# MCUio_v1_0.net
KiCad netlist of a schematic drawn in EAGLE
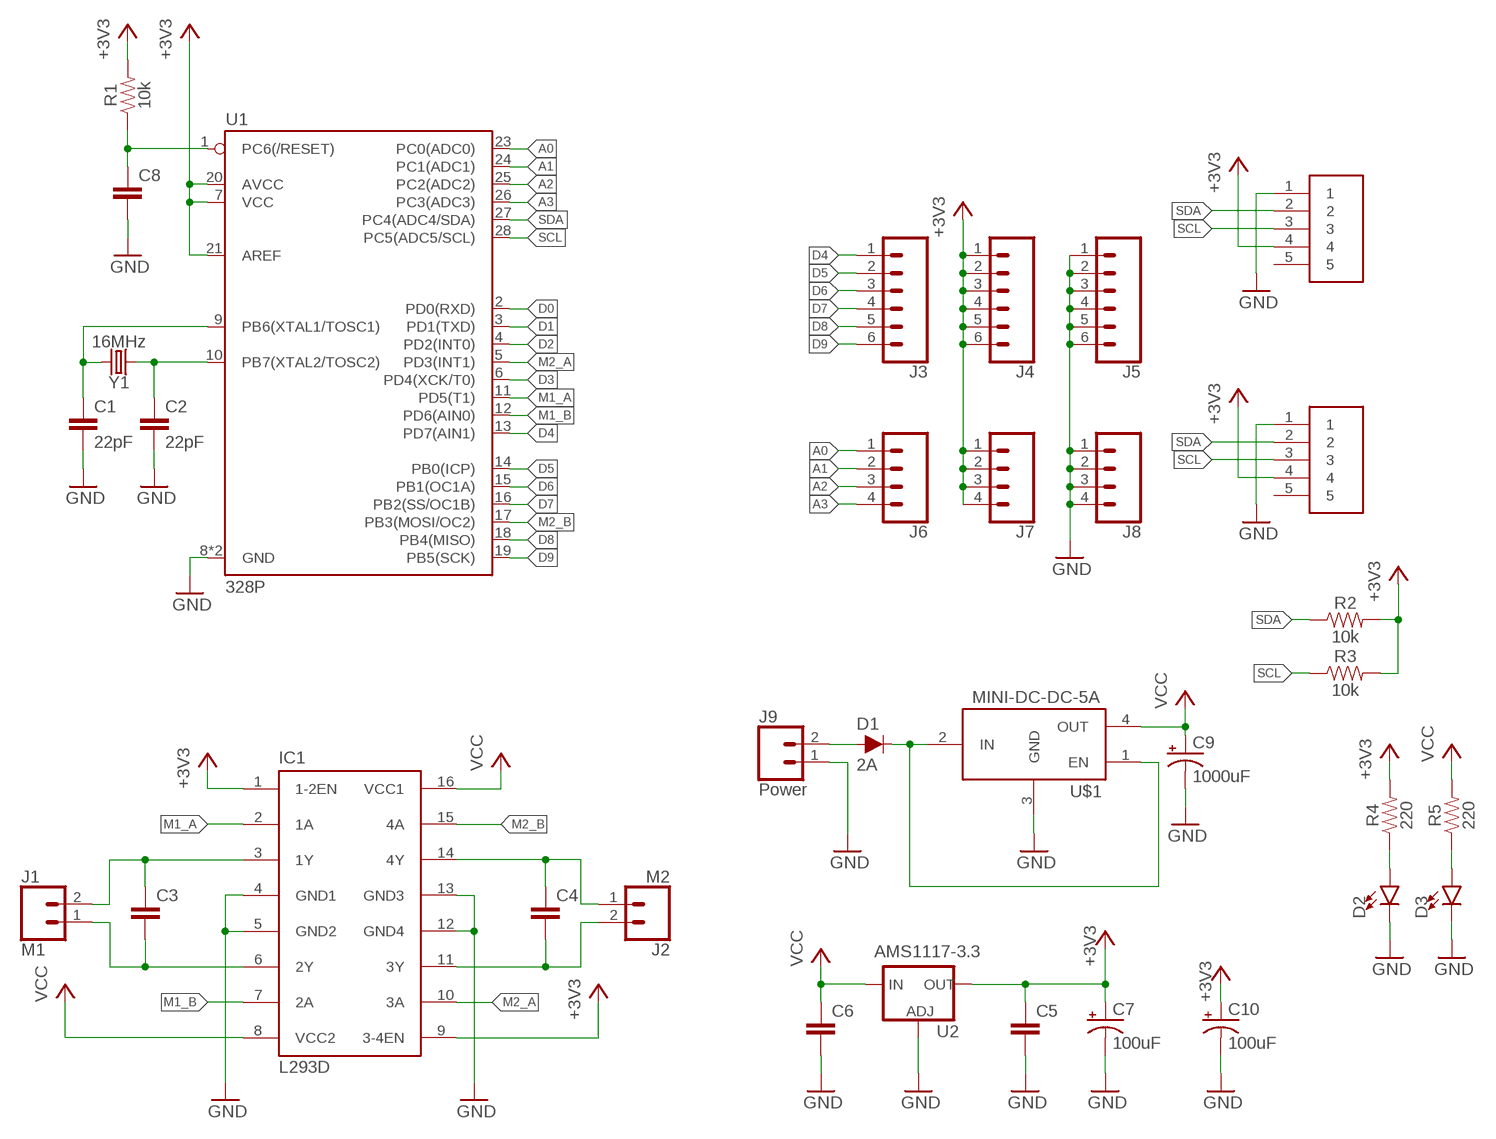
[diagram p0: schematic, sheet 1]

(export (version "E")
  (design (tool "Eeschema 10.0.6"))
  (components
    (comp (ref "C1")
      (value "22pF")
      (footprint "eagle-import:CAP-PTH-2.54")
      (libsource (lib "eagle-import") (part "22PF-PTH-2.54MM-200V-5%"))
    )
    (comp (ref "C2")
      (value "22pF")
      (footprint "eagle-import:CAP-PTH-2.54")
      (libsource (lib "eagle-import") (part "22PF-PTH-2.54MM-200V-5%"))
    )
    (comp (ref "C3")
      (value "0.1uF")
      (footprint "eagle-import:C5B2.5")
      (libsource (lib "eagle-import") (part "C5/2.5"))
    )
    (comp (ref "C4")
      (value "0.1uF")
      (footprint "eagle-import:C5B2.5")
      (libsource (lib "eagle-import") (part "C5/2.5"))
    )
    (comp (ref "C5")
      (value "0.1uF")
      (footprint "eagle-import:C5B2.5")
      (libsource (lib "eagle-import") (part "C5/2.5"))
    )
    (comp (ref "C6")
      (value "0.1uF")
      (footprint "eagle-import:C5B2.5")
      (libsource (lib "eagle-import") (part "C5/2.5"))
    )
    (comp (ref "C7")
      (value "100uF")
      (footprint "eagle-import:CPOL-RADIAL-2.5MM-6.5MM")
      (libsource (lib "eagle-import") (part "100UF-POLAR-RADIAL-2.5MM-25V-20%"))
    )
    (comp (ref "C8")
      (value "0.1uF")
      (footprint "eagle-import:C5B2.5")
      (libsource (lib "eagle-import") (part "C5/2.5"))
    )
    (comp (ref "C9")
      (value "1000uF")
      (footprint "eagle-import:CPOL-RADIAL-5MM-10MM")
      (libsource (lib "eagle-import") (part "1000UF-RADIAL-5MM-25V-20%"))
    )
    (comp (ref "C10")
      (value "100uF")
      (footprint "eagle-import:CPOL-RADIAL-2.5MM-6.5MM")
      (libsource (lib "eagle-import") (part "100UF-POLAR-RADIAL-2.5MM-25V-20%"))
    )
    (comp (ref "D1")
      (value "2A")
      (footprint "eagle-import:DIODE-1N4001-KIT")
      (libsource (lib "eagle-import") (part "DIODE-KIT2"))
    )
    (comp (ref "D2")
      (value "LED3MM")
      (footprint "eagle-import:LED_3MM")
      (libsource (lib "eagle-import") (part "LED3MM"))
    )
    (comp (ref "D3")
      (value "LED3MM")
      (footprint "eagle-import:LED_3MM")
      (libsource (lib "eagle-import") (part "LED3MM"))
    )
    (comp (ref "IC1")
      (value "L293D")
      (footprint "eagle-import:DIL16")
      (libsource (lib "eagle-import") (part "L293D"))
    )
    (comp (ref "J1")
      (value "M1")
      (footprint "eagle-import:SCREWTERMINAL-5MM-2")
      (libsource (lib "eagle-import") (part "CONN_025MM"))
    )
    (comp (ref "J2")
      (value "M2")
      (footprint "eagle-import:SCREWTERMINAL-5MM-2")
      (libsource (lib "eagle-import") (part "CONN_025MM"))
    )
    (comp (ref "J3")
      (value "CONN_06SILK_FEMALE_PTH")
      (footprint "eagle-import:1X06")
      (libsource (lib "eagle-import") (part "CONN_06SILK_FEMALE_PTH"))
    )
    (comp (ref "J4")
      (value "CONN_06SILK_FEMALE_PTH")
      (footprint "eagle-import:1X06")
      (libsource (lib "eagle-import") (part "CONN_06SILK_FEMALE_PTH"))
    )
    (comp (ref "J5")
      (value "CONN_06SILK_FEMALE_PTH")
      (footprint "eagle-import:1X06")
      (libsource (lib "eagle-import") (part "CONN_06SILK_FEMALE_PTH"))
    )
    (comp (ref "J6")
      (value "CONN_04PTH")
      (footprint "eagle-import:1X04")
      (libsource (lib "eagle-import") (part "CONN_04PTH"))
    )
    (comp (ref "J7")
      (value "CONN_04PTH")
      (footprint "eagle-import:1X04")
      (libsource (lib "eagle-import") (part "CONN_04PTH"))
    )
    (comp (ref "J8")
      (value "CONN_04PTH")
      (footprint "eagle-import:1X04")
      (libsource (lib "eagle-import") (part "CONN_04PTH"))
    )
    (comp (ref "J9")
      (value "Power")
      (footprint "eagle-import:SCREWTERMINAL-5MM-2")
      (libsource (lib "eagle-import") (part "CONN_025MM"))
    )
    (comp (ref "R1")
      (value "10k")
      (footprint "eagle-import:AXIAL-0.3")
      (libsource (lib "eagle-import") (part "10KOHM-HORIZ-1/4W-5%"))
    )
    (comp (ref "R2")
      (value "10k")
      (footprint "eagle-import:AXIAL-0.3")
      (libsource (lib "eagle-import") (part "10KOHM-HORIZ-1/4W-5%"))
    )
    (comp (ref "R3")
      (value "10k")
      (footprint "eagle-import:AXIAL-0.3")
      (libsource (lib "eagle-import") (part "10KOHM-HORIZ-1/4W-5%"))
    )
    (comp (ref "R4")
      (value "220")
      (footprint "eagle-import:0603")
      (libsource (lib "eagle-import") (part "220OHM-0603-1/10W-1%"))
    )
    (comp (ref "R5")
      (value "220")
      (footprint "eagle-import:0603")
      (libsource (lib "eagle-import") (part "220OHM-0603-1/10W-1%"))
    )
    (comp (ref "U$1")
      (value "MINI-DC-DC-5A")
      (footprint "eagle-import:MINI-DC-DC-3A")
      (libsource (lib "eagle-import") (part "MINI-DC-DC-5A"))
    )
    (comp (ref "U$2")
      (value "JST5PIN")
      (footprint "eagle-import:JST5PIN")
      (libsource (lib "eagle-import") (part "JST5PIN"))
    )
    (comp (ref "U$3")
      (value "JST5PIN")
      (footprint "eagle-import:JST5PIN")
      (libsource (lib "eagle-import") (part "JST5PIN"))
    )
    (comp (ref "U1")
      (value "328P")
      (footprint "eagle-import:DIP28")
      (libsource (lib "eagle-import") (part "ATMEGA328P_PDIP"))
    )
    (comp (ref "U2")
      (value "AMS1117-3.3")
      (footprint "eagle-import:SOT223")
      (libsource (lib "eagle-import") (part "V_REG_LM1117SOT223"))
    )
    (comp (ref "Y1")
      (value "16MHz")
      (footprint "eagle-import:HC49US")
      (libsource (lib "eagle-import") (part "CRYSTAL-16MHZPTH-HC49US"))
    )
  )
  (nets
    (net (code "1") (name "+3V3") (class "Default")
      (node (ref "C10") (pin "1") (pinfunction "+_1") (pintype "passive"))
      (node (ref "C5") (pin "1") (pinfunction "1_1") (pintype "passive"))
      (node (ref "C7") (pin "1") (pinfunction "+_1") (pintype "passive"))
      (node (ref "IC1") (pin "1") (pinfunction "1-2EN_1") (pintype "input"))
      (node (ref "IC1") (pin "9") (pinfunction "3-4EN_9") (pintype "input"))
      (node (ref "J4") (pin "1") (pinfunction "1_1") (pintype "passive"))
      (node (ref "J4") (pin "2") (pinfunction "2_2") (pintype "passive"))
      (node (ref "J4") (pin "3") (pinfunction "3_3") (pintype "passive"))
      (node (ref "J4") (pin "4") (pinfunction "4_4") (pintype "passive"))
      (node (ref "J4") (pin "5") (pinfunction "5_5") (pintype "passive"))
      (node (ref "J4") (pin "6") (pinfunction "6_6") (pintype "passive"))
      (node (ref "J7") (pin "1") (pinfunction "1_1") (pintype "passive"))
      (node (ref "J7") (pin "2") (pinfunction "2_2") (pintype "passive"))
      (node (ref "J7") (pin "3") (pinfunction "3_3") (pintype "passive"))
      (node (ref "J7") (pin "4") (pinfunction "4_4") (pintype "passive"))
      (node (ref "R1") (pin "P$2") (pinfunction "2_P$2") (pintype "passive"))
      (node (ref "R2") (pin "P$2") (pinfunction "2_P$2") (pintype "passive"))
      (node (ref "R3") (pin "P$2") (pinfunction "2_P$2") (pintype "passive"))
      (node (ref "R4") (pin "2") (pinfunction "2_2") (pintype "passive"))
      (node (ref "U$2") (pin "4") (pinfunction "4_4") (pintype "bidirectional"))
      (node (ref "U$3") (pin "4") (pinfunction "4_4") (pintype "bidirectional"))
      (node (ref "U1") (pin "20") (pinfunction "AVCC_20") (pintype "bidirectional"))
      (node (ref "U1") (pin "21") (pinfunction "AREF_21") (pintype "bidirectional"))
      (node (ref "U1") (pin "7") (pinfunction "VCC_7") (pintype "bidirectional"))
      (node (ref "U2") (pin "2") (pinfunction "OUT_2") (pintype "output"))
      (node (ref "U2") (pin "4") (pinfunction "OUT_4") (pintype "output"))
    )
    (net (code "2") (name "A0") (class "Default")
      (node (ref "J6") (pin "1") (pinfunction "1_1") (pintype "passive"))
      (node (ref "U1") (pin "23") (pinfunction "PC0(ADC0)_23") (pintype "bidirectional"))
    )
    (net (code "3") (name "A1") (class "Default")
      (node (ref "J6") (pin "2") (pinfunction "2_2") (pintype "passive"))
      (node (ref "U1") (pin "24") (pinfunction "PC1(ADC1)_24") (pintype "bidirectional"))
    )
    (net (code "4") (name "A2") (class "Default")
      (node (ref "J6") (pin "3") (pinfunction "3_3") (pintype "passive"))
      (node (ref "U1") (pin "25") (pinfunction "PC2(ADC2)_25") (pintype "bidirectional"))
    )
    (net (code "5") (name "A3") (class "Default")
      (node (ref "J6") (pin "4") (pinfunction "4_4") (pintype "passive"))
      (node (ref "U1") (pin "26") (pinfunction "PC3(ADC3)_26") (pintype "bidirectional"))
    )
    (net (code "6") (name "D0") (class "Default")
      (node (ref "U1") (pin "2") (pinfunction "PD0(RXD)_2") (pintype "bidirectional"))
    )
    (net (code "7") (name "D1") (class "Default")
      (node (ref "U1") (pin "3") (pinfunction "PD1(TXD)_3") (pintype "bidirectional"))
    )
    (net (code "8") (name "D2") (class "Default")
      (node (ref "U1") (pin "4") (pinfunction "PD2(INT0)_4") (pintype "bidirectional"))
    )
    (net (code "9") (name "D3") (class "Default")
      (node (ref "U1") (pin "6") (pinfunction "PD4(XCK/T0)_6") (pintype "bidirectional"))
    )
    (net (code "10") (name "D4") (class "Default")
      (node (ref "J3") (pin "1") (pinfunction "1_1") (pintype "passive"))
      (node (ref "U1") (pin "13") (pinfunction "PD7(AIN1)_13") (pintype "bidirectional"))
    )
    (net (code "11") (name "D5") (class "Default")
      (node (ref "J3") (pin "2") (pinfunction "2_2") (pintype "passive"))
      (node (ref "U1") (pin "14") (pinfunction "PB0(ICP)_14") (pintype "bidirectional"))
    )
    (net (code "12") (name "D6") (class "Default")
      (node (ref "J3") (pin "3") (pinfunction "3_3") (pintype "passive"))
      (node (ref "U1") (pin "15") (pinfunction "PB1(OC1A)_15") (pintype "bidirectional"))
    )
    (net (code "13") (name "D7") (class "Default")
      (node (ref "J3") (pin "4") (pinfunction "4_4") (pintype "passive"))
      (node (ref "U1") (pin "16") (pinfunction "PB2(SS/OC1B)_16") (pintype "bidirectional"))
    )
    (net (code "14") (name "D8") (class "Default")
      (node (ref "J3") (pin "5") (pinfunction "5_5") (pintype "passive"))
      (node (ref "U1") (pin "18") (pinfunction "PB4(MISO)_18") (pintype "bidirectional"))
    )
    (net (code "15") (name "D9") (class "Default")
      (node (ref "J3") (pin "6") (pinfunction "6_6") (pintype "passive"))
      (node (ref "U1") (pin "19") (pinfunction "PB5(SCK)_19") (pintype "bidirectional"))
    )
    (net (code "16") (name "GND") (class "Default")
      (node (ref "C1") (pin "2") (pinfunction "2_2") (pintype "passive"))
      (node (ref "C10") (pin "2") (pinfunction "-_2") (pintype "passive"))
      (node (ref "C2") (pin "2") (pinfunction "2_2") (pintype "passive"))
      (node (ref "C5") (pin "2") (pinfunction "2_2") (pintype "passive"))
      (node (ref "C6") (pin "2") (pinfunction "2_2") (pintype "passive"))
      (node (ref "C7") (pin "2") (pinfunction "-_2") (pintype "passive"))
      (node (ref "C8") (pin "2") (pinfunction "2_2") (pintype "passive"))
      (node (ref "C9") (pin "-") (pinfunction "-_-") (pintype "passive"))
      (node (ref "D2") (pin "K") (pinfunction "C_K") (pintype "passive"))
      (node (ref "D3") (pin "K") (pinfunction "C_K") (pintype "passive"))
      (node (ref "IC1") (pin "12") (pinfunction "GND4_12") (pintype "power_in"))
      (node (ref "IC1") (pin "13") (pinfunction "GND3_13") (pintype "power_in"))
      (node (ref "IC1") (pin "4") (pinfunction "GND1_4") (pintype "power_in"))
      (node (ref "IC1") (pin "5") (pinfunction "GND2_5") (pintype "power_in"))
      (node (ref "J5") (pin "1") (pinfunction "1_1") (pintype "passive"))
      (node (ref "J5") (pin "2") (pinfunction "2_2") (pintype "passive"))
      (node (ref "J5") (pin "3") (pinfunction "3_3") (pintype "passive"))
      (node (ref "J5") (pin "4") (pinfunction "4_4") (pintype "passive"))
      (node (ref "J5") (pin "5") (pinfunction "5_5") (pintype "passive"))
      (node (ref "J5") (pin "6") (pinfunction "6_6") (pintype "passive"))
      (node (ref "J8") (pin "1") (pinfunction "1_1") (pintype "passive"))
      (node (ref "J8") (pin "2") (pinfunction "2_2") (pintype "passive"))
      (node (ref "J8") (pin "3") (pinfunction "3_3") (pintype "passive"))
      (node (ref "J8") (pin "4") (pinfunction "4_4") (pintype "passive"))
      (node (ref "J9") (pin "1") (pinfunction "1_1") (pintype "passive"))
      (node (ref "U$1") (pin "3") (pinfunction "GND_3") (pintype "bidirectional"))
      (node (ref "U$2") (pin "1") (pinfunction "1_1") (pintype "bidirectional"))
      (node (ref "U$3") (pin "1") (pinfunction "1_1") (pintype "bidirectional"))
      (node (ref "U1") (pin "22") (pinfunction "GND_22") (pintype "bidirectional"))
      (node (ref "U1") (pin "8") (pinfunction "GND_8") (pintype "bidirectional"))
      (node (ref "U2") (pin "1") (pinfunction "ADJ_1") (pintype "input"))
    )
    (net (code "17") (name "M1_A") (class "Default")
      (node (ref "IC1") (pin "2") (pinfunction "1A_2") (pintype "input"))
      (node (ref "U1") (pin "11") (pinfunction "PD5(T1)_11") (pintype "bidirectional"))
    )
    (net (code "18") (name "M1_B") (class "Default")
      (node (ref "IC1") (pin "7") (pinfunction "2A_7") (pintype "input"))
      (node (ref "U1") (pin "12") (pinfunction "PD6(AIN0)_12") (pintype "bidirectional"))
    )
    (net (code "19") (name "M2_A") (class "Default")
      (node (ref "IC1") (pin "10") (pinfunction "3A_10") (pintype "input"))
      (node (ref "U1") (pin "5") (pinfunction "PD3(INT1)_5") (pintype "bidirectional"))
    )
    (net (code "20") (name "M2_B") (class "Default")
      (node (ref "IC1") (pin "15") (pinfunction "4A_15") (pintype "input"))
      (node (ref "U1") (pin "17") (pinfunction "PB3(MOSI/OC2)_17") (pintype "bidirectional"))
    )
    (net (code "21") (name "Net-(D1-PadA)") (class "Default")
      (node (ref "D1") (pin "A") (pinfunction "A_A") (pintype "passive"))
      (node (ref "J9") (pin "2") (pinfunction "2_2") (pintype "passive"))
    )
    (net (code "22") (name "Net-(D2-PadA)") (class "Default")
      (node (ref "D2") (pin "A") (pinfunction "A_A") (pintype "passive"))
      (node (ref "R4") (pin "1") (pinfunction "1_1") (pintype "passive"))
    )
    (net (code "23") (name "Net-(D3-PadA)") (class "Default")
      (node (ref "D3") (pin "A") (pinfunction "A_A") (pintype "passive"))
      (node (ref "R5") (pin "1") (pinfunction "1_1") (pintype "passive"))
    )
    (net (code "24") (name "Net-(IC1-1Y)") (class "Default")
      (node (ref "C3") (pin "1") (pinfunction "1_1") (pintype "passive"))
      (node (ref "IC1") (pin "3") (pinfunction "1Y_3") (pintype "output"))
      (node (ref "J1") (pin "2") (pinfunction "2_2") (pintype "passive"))
    )
    (net (code "25") (name "Net-(IC1-2Y)") (class "Default")
      (node (ref "C3") (pin "2") (pinfunction "2_2") (pintype "passive"))
      (node (ref "IC1") (pin "6") (pinfunction "2Y_6") (pintype "output"))
      (node (ref "J1") (pin "1") (pinfunction "1_1") (pintype "passive"))
    )
    (net (code "26") (name "Net-(IC1-3Y)") (class "Default")
      (node (ref "C4") (pin "2") (pinfunction "2_2") (pintype "passive"))
      (node (ref "IC1") (pin "11") (pinfunction "3Y_11") (pintype "output"))
      (node (ref "J2") (pin "2") (pinfunction "2_2") (pintype "passive"))
    )
    (net (code "27") (name "Net-(IC1-4Y)") (class "Default")
      (node (ref "C4") (pin "1") (pinfunction "1_1") (pintype "passive"))
      (node (ref "IC1") (pin "14") (pinfunction "4Y_14") (pintype "output"))
      (node (ref "J2") (pin "1") (pinfunction "1_1") (pintype "passive"))
    )
    (net (code "28") (name "Net-(R1-1)") (class "Default")
      (node (ref "C8") (pin "1") (pinfunction "1_1") (pintype "passive"))
      (node (ref "R1") (pin "P$1") (pinfunction "1_P$1") (pintype "passive"))
      (node (ref "U1") (pin "1") (pinfunction "PC6(/RESET)_1") (pintype "bidirectional"))
    )
    (net (code "29") (name "Net-(U$1-EN)") (class "Default")
      (node (ref "D1") (pin "C") (pinfunction "C_C") (pintype "passive"))
      (node (ref "U$1") (pin "1") (pinfunction "EN_1") (pintype "bidirectional"))
      (node (ref "U$1") (pin "2") (pinfunction "IN_2") (pintype "bidirectional"))
    )
    (net (code "30") (name "Net-(U1-PB6(XTAL1{slash}TOSC1))") (class "Default")
      (node (ref "C1") (pin "1") (pinfunction "1_1") (pintype "passive"))
      (node (ref "U1") (pin "9") (pinfunction "PB6(XTAL1/TOSC1)_9") (pintype "bidirectional"))
      (node (ref "Y1") (pin "2") (pinfunction "2_2") (pintype "passive"))
    )
    (net (code "31") (name "Net-(U1-PB7(XTAL2{slash}TOSC2))") (class "Default")
      (node (ref "C2") (pin "1") (pinfunction "1_1") (pintype "passive"))
      (node (ref "U1") (pin "10") (pinfunction "PB7(XTAL2/TOSC2)_10") (pintype "bidirectional"))
      (node (ref "Y1") (pin "1") (pinfunction "1_1") (pintype "passive"))
    )
    (net (code "32") (name "SCL") (class "Default")
      (node (ref "R3") (pin "P$1") (pinfunction "1_P$1") (pintype "passive"))
      (node (ref "U$2") (pin "3") (pinfunction "3_3") (pintype "bidirectional"))
      (node (ref "U$3") (pin "3") (pinfunction "3_3") (pintype "bidirectional"))
      (node (ref "U1") (pin "28") (pinfunction "PC5(ADC5/SCL)_28") (pintype "bidirectional"))
    )
    (net (code "33") (name "SDA") (class "Default")
      (node (ref "R2") (pin "P$1") (pinfunction "1_P$1") (pintype "passive"))
      (node (ref "U$2") (pin "2") (pinfunction "2_2") (pintype "bidirectional"))
      (node (ref "U$3") (pin "2") (pinfunction "2_2") (pintype "bidirectional"))
      (node (ref "U1") (pin "27") (pinfunction "PC4(ADC4/SDA)_27") (pintype "bidirectional"))
    )
    (net (code "34") (name "VCC") (class "Default")
      (node (ref "C6") (pin "1") (pinfunction "1_1") (pintype "passive"))
      (node (ref "C9") (pin "+") (pinfunction "+_+") (pintype "passive"))
      (node (ref "IC1") (pin "16") (pinfunction "VCC1_16") (pintype "power_in"))
      (node (ref "IC1") (pin "8") (pinfunction "VCC2_8") (pintype "power_in"))
      (node (ref "R5") (pin "2") (pinfunction "2_2") (pintype "passive"))
      (node (ref "U$1") (pin "4") (pinfunction "OUT_4") (pintype "bidirectional"))
      (node (ref "U2") (pin "3") (pinfunction "IN_3") (pintype "input"))
    )
    (net (code "35") (name "unconnected-(U$2-Pad5)") (class "Default")
      (node (ref "U$2") (pin "5") (pinfunction "5_5") (pintype "bidirectional"))
    )
    (net (code "36") (name "unconnected-(U$3-Pad5)") (class "Default")
      (node (ref "U$3") (pin "5") (pinfunction "5_5") (pintype "bidirectional"))
    )
  )
)
